# BalCircuit.net
KiCad netlist of a schematic drawn in Altium Designer
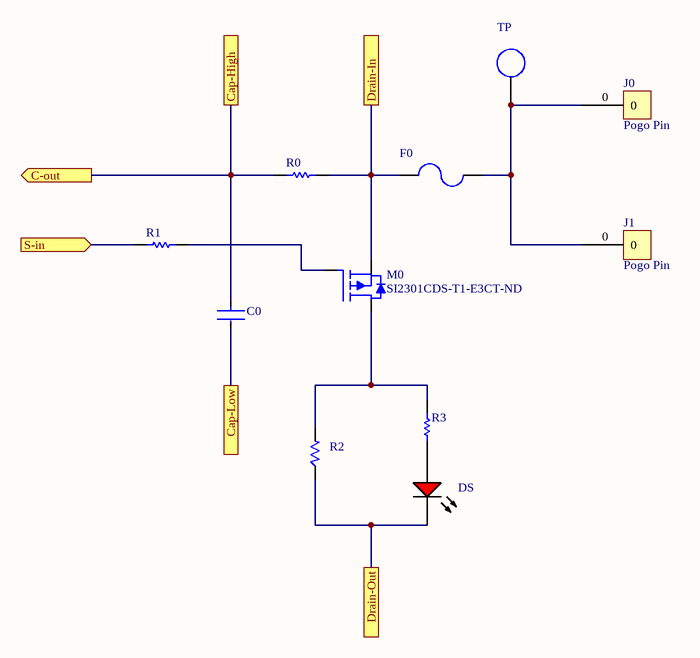
[diagram p0: BalCircuit.SchDoc]

(export (version "E")
  (design (tool "Eeschema 10.0.6"))
  (components
    (comp (ref "C0")
      (value "CL21B103KCANNNC")
      (footprint "FP-CL21-IPC_A")
      (description "CL21 Series 0805 10nF 100V ±10% Tolerance X7R Multilayer Ceramic Chip Capacitor")
      (fields (field (name "VOLTAGE") "100V") (field (name "TOLERANCE") "10%"))
      (libsource (lib "Altium Content Vault") (part "b4654b650e69147ec39a6b967a45e02"))
    )
    (comp (ref "DS")
      (value "19-217/R6C-AL1M2VY/3T")
      (footprint "EVRL-0603-2_V")
      (description "Chip LED, Red, 5 V, 25 mA, -40 to 85 degC, 2-Pin SMD (0603), RoHS, Tape and Reel")
      (fields (field (name "MANUFACTURER") "Everlight Electronics"))
      (libsource (lib "Altium Content Vault") (part "LED-RED-AK-2"))
    )
    (comp (ref "F0")
      (value "3404.0112.11")
      (footprint "OMT125")
      (description "SCHURTER   3404.0112.11   FUSE, 1/2A, 125VDC, SMT")
      (libsource (lib "otherComponents") (part "OMT125"))
    )
    (comp (ref "J0")
      (value "Pogo Pin")
      (footprint "0852-0")
      (description "90 thou stroke")
      (libsource (lib "SinglePad") (part "0852-0-15-20-83-14-11-0"))
    )
    (comp (ref "J1")
      (value "Pogo Pin")
      (footprint "0852-0")
      (description "90 thou stroke")
      (libsource (lib "SinglePad") (part "0852-0-15-20-83-14-11-0"))
    )
    (comp (ref "M0")
      (value "SI2301CDS-T1-E3")
      (footprint "SOT23_527AG_ONS")
      (description "Trans Mosfet P-ch 20V 3.1A 3-PIN SOT-23 T/r / Mosfet P-ch 20V 3.1A SOT23-3")
      (fields (field (name "SUPPLIER PART NUMBER 1") "SI2301CDS-T1-E3CT-ND"))
      (libsource (lib "otherComponents") (part "SI2301CDS-T1-E3"))
    )
    (comp (ref "R0")
      (value "RK73B2ATTD101J")
      (footprint "RESC2013X60X30NL20T20")
      (description "100R 1/4W 5% 0805")
      (fields (field (name "MANUFACTURER") "KOA Speer"))
      (libsource (lib "Altium Content Vault") (part "RES"))
    )
    (comp (ref "R1")
      (value "RC0805JR-073K3L")
      (footprint "RESC0805(2012)_M")
      (description "3K3 0.125W 5% 0805 (2012 Metric)  SMD")
      (fields (field (name "TOLERANCE") "5 %") (field (name "POWER") "0.125 W"))
      (libsource (lib "Altium Content Vault") (part "RES"))
    )
    (comp (ref "R2")
      (value "352116RFT")
      (footprint "FP-ERJ1TR-IPC_A")
      (description "Res Thick Film 2512 16 Ohm 1% 2W ±100ppm/C Pad SMD Automotive T/R")
      (fields (field (name "TOLERANCE") "1%"))
      (libsource (lib "Resistors") (part "352116RFT"))
    )
    (comp (ref "R3")
      (value "0603WAF750JT5E")
      (footprint "FP-AC0603-0_55-MFG")
      (description "±1% ±200ppm/℃ 75Ω 0.1W 0603 Chip Resistor - Surface Mount ROHS")
      (fields (field (name "TOLERANCE") "0.1%"))
      (libsource (lib "Resistors") (part "0603WAF750JT5E"))
    )
    (comp (ref "TP")
      (value "N/A")
      (footprint "PCB Test Point")
      (description "PCB Test Point")
      (fields (field (name "MANUFACTURER") "RIT Racing") (field (name "PUBLISHER") "T.Tallo"))
      (libsource (lib "Connectors") (part "PCB Test Point"))
    )
  )
  (nets
    (net (code "1") (name "/C-out") (class "Default")
      (node (ref "C0") (pin "1") (pinfunction "1_1") (pintype "passive"))
      (node (ref "R0") (pin "1") (pinfunction "1_1") (pintype "passive"))
    )
    (net (code "2") (name "/Cap-Low") (class "Default")
      (node (ref "C0") (pin "2") (pinfunction "2_2") (pintype "passive"))
    )
    (net (code "3") (name "/Drain-In") (class "Default")
      (node (ref "F0") (pin "1") (pinfunction "1_1") (pintype "passive"))
      (node (ref "M0") (pin "2") (pinfunction "2_2") (pintype "passive"))
      (node (ref "R0") (pin "2") (pinfunction "2_2") (pintype "passive"))
    )
    (net (code "4") (name "/Drain-Out") (class "Default")
      (node (ref "DS") (pin "2") (pinfunction "K_2") (pintype "passive"))
      (node (ref "R2") (pin "1") (pinfunction "1_1") (pintype "passive"))
    )
    (net (code "5") (name "/S-in") (class "Default")
      (node (ref "R1") (pin "1") (pinfunction "1_1") (pintype "passive"))
    )
    (net (code "6") (name "Net-(DS-A)") (class "Default")
      (node (ref "DS") (pin "1") (pinfunction "A_1") (pintype "passive"))
      (node (ref "R3") (pin "2") (pinfunction "2_2") (pintype "passive"))
    )
    (net (code "7") (name "Net-(F0-Pad2)") (class "Default")
      (node (ref "F0") (pin "2") (pinfunction "2_2") (pintype "passive"))
      (node (ref "J0") (pin "0") (pinfunction "0_0") (pintype "passive"))
      (node (ref "J1") (pin "0") (pinfunction "0_0") (pintype "passive"))
      (node (ref "TP") (pin "1") (pinfunction "1_1") (pintype "passive"))
    )
    (net (code "8") (name "Net-(M0-Pad1)") (class "Default")
      (node (ref "M0") (pin "1") (pinfunction "1_1") (pintype "passive"))
      (node (ref "R1") (pin "2") (pinfunction "2_2") (pintype "passive"))
    )
    (net (code "9") (name "Net-(M0-Pad3)") (class "Default")
      (node (ref "M0") (pin "3") (pinfunction "3_3") (pintype "passive"))
      (node (ref "R2") (pin "2") (pinfunction "2_2") (pintype "passive"))
      (node (ref "R3") (pin "1") (pinfunction "1_1") (pintype "passive"))
    )
  )
)
